# EasyFlybackRev2.net
KiCad netlist of a schematic drawn in EAGLE
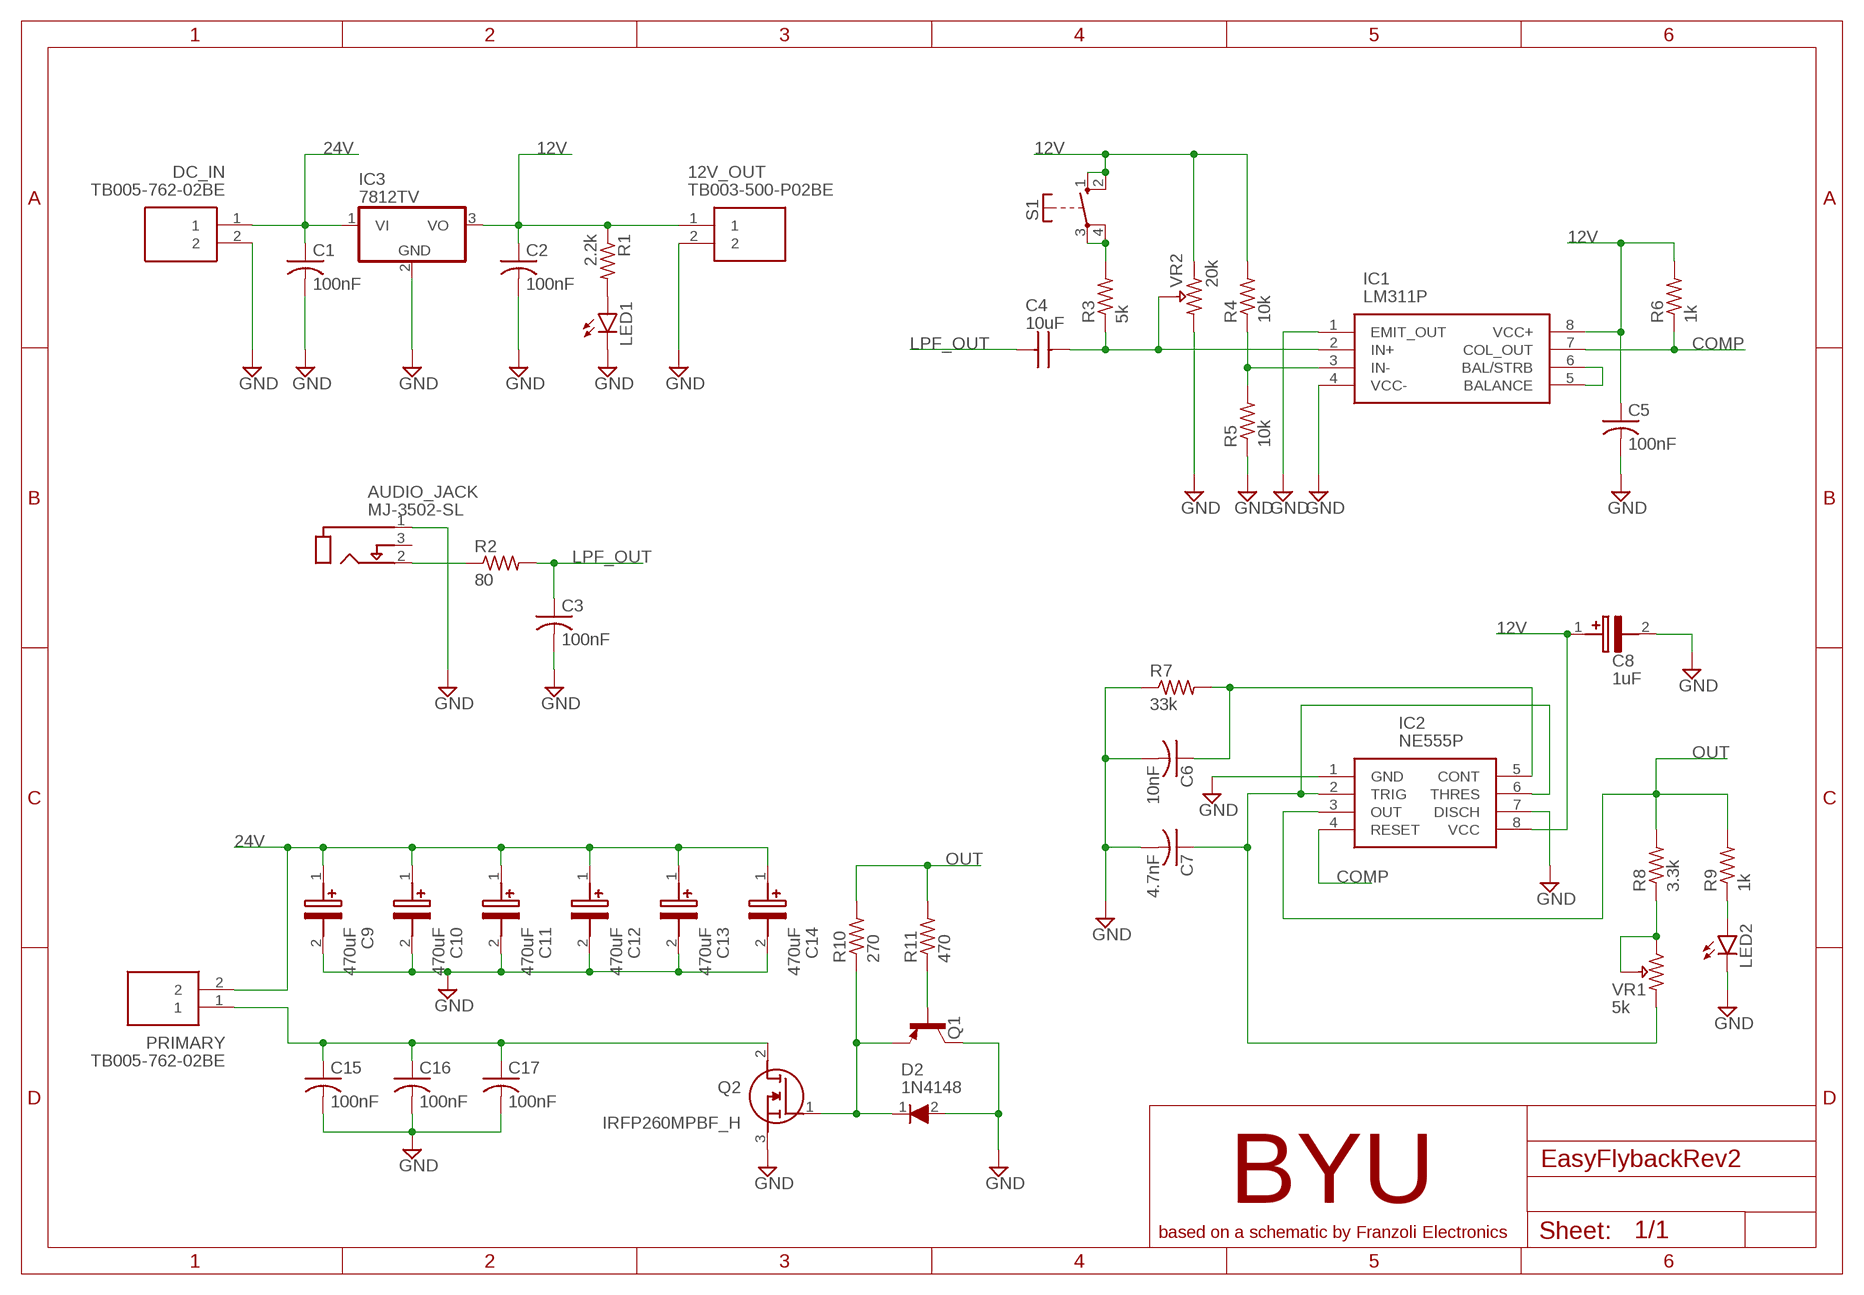
[diagram p0: schematic, sheet 1]

(export (version "E")
  (design (tool "Eeschema 10.0.6"))
  (components
    (comp (ref "12V_OUT")
      (value "TB003-500-P02BE")
      (footprint "eagle-import:SHDR2W100P0X500_1X2_1000X780X1")
      (fields (field (name "MOUSER_PART_NUMBER") "490-TB003-500-P02BE"))
      (libsource (lib "eagle-import") (part "TB003-500-P02BE"))
    )
    (comp (ref "AUDIO_JACK")
      (value "MJ-3502-SL")
      (footprint "eagle-import:MJ3502-SL")
      (fields (field (name "SPICEPREFIX") "J"))
      (libsource (lib "eagle-import") (part "MJ-3502-SL"))
    )
    (comp (ref "C1")
      (value "100nF")
      (footprint "eagle-import:C025-024X044")
      (libsource (lib "eagle-import") (part "C-US025-024X044"))
    )
    (comp (ref "C2")
      (value "100nF")
      (footprint "eagle-import:C025-024X044")
      (libsource (lib "eagle-import") (part "C-US025-024X044"))
    )
    (comp (ref "C3")
      (value "100nF")
      (footprint "eagle-import:C025-024X044")
      (libsource (lib "eagle-import") (part "C-US025-024X044"))
    )
    (comp (ref "C4")
      (value "10uF")
      (footprint "eagle-import:RCE7U2J103J3K1H03B")
      (fields
        (field (name "MANUFACTURER_PART_NUMBER") "RDEC71H106K3K1H03B")
        (field (name "MOUSER_PART_NUMBER") "81-RDEC71H106K3K1H3B")
      )
      (libsource (lib "eagle-import") (part "RDEC71H106K3K1H03B"))
    )
    (comp (ref "C5")
      (value "100nF")
      (footprint "eagle-import:C025-024X044")
      (libsource (lib "eagle-import") (part "C-US025-024X044"))
    )
    (comp (ref "C6")
      (value "10nF")
      (footprint "eagle-import:C025-024X044")
      (libsource (lib "eagle-import") (part "C-US025-024X044"))
    )
    (comp (ref "C7")
      (value "4.7nF")
      (footprint "eagle-import:C025-024X044")
      (libsource (lib "eagle-import") (part "C-US025-024X044"))
    )
    (comp (ref "C8")
      (value "1uF")
      (footprint "eagle-import:TAP105K035SCS")
      (fields
        (field (name "MANUFACTURER_PART_NUMBER") "TAP105K035SCS")
        (field (name "MOUSER_PART_NUMBER") "581-TAP105K035SCS")
      )
      (libsource (lib "eagle-import") (part "TAP105K035SCS"))
    )
    (comp (ref "C9")
      (value "470uF")
      (footprint "eagle-import:CAPPRD500W65D1000H1700")
      (fields
        (field (name "MANUFACTURER_PART_NUMBER") "ECA-1VM471B")
        (field (name "MOUSER_PART_NUMBER") "667-ECA-1VM471B")
      )
      (libsource (lib "eagle-import") (part "ECA-1VM471B"))
    )
    (comp (ref "C10")
      (value "470uF")
      (footprint "eagle-import:CAPPRD500W65D1000H1700")
      (fields
        (field (name "MANUFACTURER_PART_NUMBER") "ECA-1VM471B")
        (field (name "MOUSER_PART_NUMBER") "667-ECA-1VM471B")
      )
      (libsource (lib "eagle-import") (part "ECA-1VM471B"))
    )
    (comp (ref "C11")
      (value "470uF")
      (footprint "eagle-import:CAPPRD500W65D1000H1700")
      (fields
        (field (name "MANUFACTURER_PART_NUMBER") "ECA-1VM471B")
        (field (name "MOUSER_PART_NUMBER") "667-ECA-1VM471B")
      )
      (libsource (lib "eagle-import") (part "ECA-1VM471B"))
    )
    (comp (ref "C12")
      (value "470uF")
      (footprint "eagle-import:CAPPRD500W65D1000H1700")
      (fields
        (field (name "MANUFACTURER_PART_NUMBER") "ECA-1VM471B")
        (field (name "MOUSER_PART_NUMBER") "667-ECA-1VM471B")
      )
      (libsource (lib "eagle-import") (part "ECA-1VM471B"))
    )
    (comp (ref "C13")
      (value "470uF")
      (footprint "eagle-import:CAPPRD500W65D1000H1700")
      (fields
        (field (name "MANUFACTURER_PART_NUMBER") "ECA-1VM471B")
        (field (name "MOUSER_PART_NUMBER") "667-ECA-1VM471B")
      )
      (libsource (lib "eagle-import") (part "ECA-1VM471B"))
    )
    (comp (ref "C14")
      (value "470uF")
      (footprint "eagle-import:CAPPRD500W65D1000H1700")
      (fields
        (field (name "MANUFACTURER_PART_NUMBER") "ECA-1VM471B")
        (field (name "MOUSER_PART_NUMBER") "667-ECA-1VM471B")
      )
      (libsource (lib "eagle-import") (part "ECA-1VM471B"))
    )
    (comp (ref "C15")
      (value "100nF")
      (footprint "eagle-import:MKP1G031004D00KSSD")
      (libsource (lib "eagle-import") (part "MKP1G031004D00KSSD"))
    )
    (comp (ref "C16")
      (value "100nF")
      (footprint "eagle-import:MKP1G031004D00KSSD")
      (libsource (lib "eagle-import") (part "MKP1G031004D00KSSD"))
    )
    (comp (ref "C17")
      (value "100nF")
      (footprint "eagle-import:MKP1G031004D00KSSD")
      (libsource (lib "eagle-import") (part "MKP1G031004D00KSSD"))
    )
    (comp (ref "D2")
      (value "1N4148")
      (footprint "eagle-import:DIOAD1068W53L380D172")
      (fields (field (name "MOUSER_PART_NUMBER") "512-1N4148"))
      (libsource (lib "eagle-import") (part "1N4148"))
    )
    (comp (ref "DC_IN")
      (value "TB005-762-02BE")
      (footprint "eagle-import:TB00576202BE")
      (fields (field (name "MOUSER_PART_NUMBER") "490-TB005-762-02BE"))
      (libsource (lib "eagle-import") (part "TB005-762-02BE"))
    )
    (comp (ref "IC1")
      (value "LM311P")
      (footprint "eagle-import:DIP794W53P254L959H508Q8N")
      (fields (field (name "MOUSER_PART_NUMBER") "595-LM311P"))
      (libsource (lib "eagle-import") (part "LM311P"))
    )
    (comp (ref "IC2")
      (value "NE555P")
      (footprint "eagle-import:DIP794W53P254L959H508Q8N")
      (fields (field (name "MOUSER_PART_NUMBER") "595-NE555P"))
      (libsource (lib "eagle-import") (part "NE555P"))
    )
    (comp (ref "IC3")
      (value "7812TV")
      (footprint "eagle-import:TO220V")
      (libsource (lib "eagle-import") (part "78TV12"))
    )
    (comp (ref "LED1")
      (value "LED5MM")
      (footprint "eagle-import:LED5MM")
      (libsource (lib "eagle-import") (part "LED5MM"))
    )
    (comp (ref "LED2")
      (value "LED5MM")
      (footprint "eagle-import:LED5MM")
      (libsource (lib "eagle-import") (part "LED5MM"))
    )
    (comp (ref "PRIMARY")
      (value "TB005-762-02BE")
      (footprint "eagle-import:TB00576202BE")
      (fields (field (name "MOUSER_PART_NUMBER") "490-TB005-762-02BE"))
      (libsource (lib "eagle-import") (part "TB005-762-02BE"))
    )
    (comp (ref "Q1")
      (value "-PNP-TO92-E1")
      (footprint "eagle-import:TO92-E1")
      (libsource (lib "eagle-import") (part "-PNP-TO92-E1"))
    )
    (comp (ref "Q2")
      (value "IRFP260MPBF_H")
      (footprint "eagle-import:TO545P520X1594X2550-3P_H")
      (fields
        (field (name "MANUFACTURER_PART_NUMBER") "IRFP260MPBF")
        (field (name "MOUSER_PART_NUMBER") "942-IRFP260MPBF")
      )
      (libsource (lib "eagle-import") (part "IRFP260MPBF_H"))
    )
    (comp (ref "R1")
      (value "2.2k")
      (footprint "eagle-import:0207_10")
      (libsource (lib "eagle-import") (part "R-US_0207/10"))
    )
    (comp (ref "R2")
      (value "80")
      (footprint "eagle-import:0207_10")
      (libsource (lib "eagle-import") (part "R-US_0207/10"))
    )
    (comp (ref "R3")
      (value "5k")
      (footprint "eagle-import:0207_10")
      (libsource (lib "eagle-import") (part "R-US_0207/10"))
    )
    (comp (ref "R4")
      (value "10k")
      (footprint "eagle-import:0207_10")
      (libsource (lib "eagle-import") (part "R-US_0207/10"))
    )
    (comp (ref "R5")
      (value "10k")
      (footprint "eagle-import:0207_10")
      (libsource (lib "eagle-import") (part "R-US_0207/10"))
    )
    (comp (ref "R6")
      (value "1k")
      (footprint "eagle-import:0207_10")
      (libsource (lib "eagle-import") (part "R-US_0207/10"))
    )
    (comp (ref "R7")
      (value "33k")
      (footprint "eagle-import:0207_10")
      (libsource (lib "eagle-import") (part "R-US_0207/10"))
    )
    (comp (ref "R8")
      (value "3.3k")
      (footprint "eagle-import:0207_10")
      (libsource (lib "eagle-import") (part "R-US_0207/10"))
    )
    (comp (ref "R9")
      (value "1k")
      (footprint "eagle-import:0207_10")
      (libsource (lib "eagle-import") (part "R-US_0207/10"))
    )
    (comp (ref "R10")
      (value "270")
      (footprint "eagle-import:0207_10")
      (libsource (lib "eagle-import") (part "R-US_0207/10"))
    )
    (comp (ref "R11")
      (value "470")
      (footprint "eagle-import:0207_10")
      (libsource (lib "eagle-import") (part "R-US_0207/10"))
    )
    (comp (ref "S1")
      (value "DTE6K")
      (footprint "eagle-import:DTE6K")
      (libsource (lib "eagle-import") (part "DTE6K"))
    )
    (comp (ref "VR1")
      (value "5k")
      (footprint "eagle-import:PV36W502C01B00")
      (fields
        (field (name "MANUFACTURER_PART_NUMBER") "PV36W502C01B00")
        (field (name "MOUSER_PART_NUMBER") "81-PV36W502C01B00")
      )
      (libsource (lib "eagle-import") (part "PV36W502C01B00"))
    )
    (comp (ref "VR2")
      (value "20k")
      (footprint "eagle-import:PV36W502C01B00")
      (fields
        (field (name "MANUFACTURER_PART_NUMBER") "PV36W502C01B00")
        (field (name "MOUSER_PART_NUMBER") "81-PV36W502C01B00")
      )
      (libsource (lib "eagle-import") (part "PV36W502C01B00"))
    )
  )
  (nets
    (net (code "1") (name "/12V") (class "Default")
      (node (ref "12V_OUT") (pin "1") (pinfunction "1_1") (pintype "bidirectional"))
      (node (ref "C2") (pin "1") (pinfunction "1_1") (pintype "passive"))
      (node (ref "C5") (pin "1") (pinfunction "1_1") (pintype "passive"))
      (node (ref "C8") (pin "1") (pinfunction "+_1") (pintype "bidirectional"))
      (node (ref "IC1") (pin "8") (pinfunction "VCC+_8") (pintype "bidirectional"))
      (node (ref "IC2") (pin "8") (pinfunction "VCC_8") (pintype "bidirectional"))
      (node (ref "IC3") (pin "3") (pinfunction "VO_3") (pintype "passive"))
      (node (ref "R1") (pin "1") (pinfunction "1_1") (pintype "passive"))
      (node (ref "R4") (pin "2") (pinfunction "2_2") (pintype "passive"))
      (node (ref "R6") (pin "2") (pinfunction "2_2") (pintype "passive"))
      (node (ref "S1") (pin "1") (pinfunction "S_1") (pintype "passive"))
      (node (ref "S1") (pin "2") (pinfunction "S_2") (pintype "passive"))
      (node (ref "VR2") (pin "1") (pinfunction "CCW_1") (pintype "bidirectional"))
    )
    (net (code "2") (name "/24V") (class "Default")
      (node (ref "C1") (pin "1") (pinfunction "1_1") (pintype "passive"))
      (node (ref "C10") (pin "1") (pinfunction "+_1") (pintype "bidirectional"))
      (node (ref "C11") (pin "1") (pinfunction "+_1") (pintype "bidirectional"))
      (node (ref "C12") (pin "1") (pinfunction "+_1") (pintype "bidirectional"))
      (node (ref "C13") (pin "1") (pinfunction "+_1") (pintype "bidirectional"))
      (node (ref "C14") (pin "1") (pinfunction "+_1") (pintype "bidirectional"))
      (node (ref "C9") (pin "1") (pinfunction "+_1") (pintype "bidirectional"))
      (node (ref "DC_IN") (pin "1") (pinfunction "1_1") (pintype "bidirectional"))
      (node (ref "IC3") (pin "1") (pinfunction "VI_1") (pintype "input"))
      (node (ref "PRIMARY") (pin "2") (pinfunction "2_2") (pintype "bidirectional"))
    )
    (net (code "3") (name "/COMP") (class "Default")
      (node (ref "IC1") (pin "7") (pinfunction "COL_OUT_7") (pintype "bidirectional"))
      (node (ref "IC2") (pin "4") (pinfunction "RESET_4") (pintype "bidirectional"))
      (node (ref "R6") (pin "1") (pinfunction "1_1") (pintype "passive"))
    )
    (net (code "4") (name "/LPF_OUT") (class "Default")
      (node (ref "C3") (pin "1") (pinfunction "1_1") (pintype "passive"))
      (node (ref "C4") (pin "1") (pinfunction "1_1") (pintype "bidirectional"))
      (node (ref "R2") (pin "2") (pinfunction "2_2") (pintype "passive"))
    )
    (net (code "5") (name "/OUT") (class "Default")
      (node (ref "IC2") (pin "3") (pinfunction "OUT_3") (pintype "bidirectional"))
      (node (ref "R10") (pin "2") (pinfunction "2_2") (pintype "passive"))
      (node (ref "R11") (pin "2") (pinfunction "2_2") (pintype "passive"))
      (node (ref "R8") (pin "2") (pinfunction "2_2") (pintype "passive"))
      (node (ref "R9") (pin "2") (pinfunction "2_2") (pintype "passive"))
    )
    (net (code "6") (name "GND") (class "Default")
      (node (ref "12V_OUT") (pin "2") (pinfunction "2_2") (pintype "bidirectional"))
      (node (ref "AUDIO_JACK") (pin "1") (pinfunction "1_1") (pintype "bidirectional"))
      (node (ref "C1") (pin "2") (pinfunction "2_2") (pintype "passive"))
      (node (ref "C10") (pin "2") (pinfunction "-_2") (pintype "bidirectional"))
      (node (ref "C11") (pin "2") (pinfunction "-_2") (pintype "bidirectional"))
      (node (ref "C12") (pin "2") (pinfunction "-_2") (pintype "bidirectional"))
      (node (ref "C13") (pin "2") (pinfunction "-_2") (pintype "bidirectional"))
      (node (ref "C14") (pin "2") (pinfunction "-_2") (pintype "bidirectional"))
      (node (ref "C15") (pin "P$2") (pinfunction "2_P$2") (pintype "passive"))
      (node (ref "C16") (pin "P$2") (pinfunction "2_P$2") (pintype "passive"))
      (node (ref "C17") (pin "P$2") (pinfunction "2_P$2") (pintype "passive"))
      (node (ref "C2") (pin "2") (pinfunction "2_2") (pintype "passive"))
      (node (ref "C3") (pin "2") (pinfunction "2_2") (pintype "passive"))
      (node (ref "C5") (pin "2") (pinfunction "2_2") (pintype "passive"))
      (node (ref "C6") (pin "2") (pinfunction "2_2") (pintype "passive"))
      (node (ref "C7") (pin "2") (pinfunction "2_2") (pintype "passive"))
      (node (ref "C8") (pin "2") (pinfunction "-_2") (pintype "bidirectional"))
      (node (ref "C9") (pin "2") (pinfunction "-_2") (pintype "bidirectional"))
      (node (ref "D2") (pin "2") (pinfunction "A_2") (pintype "bidirectional"))
      (node (ref "DC_IN") (pin "2") (pinfunction "2_2") (pintype "bidirectional"))
      (node (ref "IC1") (pin "1") (pinfunction "EMIT_OUT_1") (pintype "bidirectional"))
      (node (ref "IC1") (pin "4") (pinfunction "VCC-_4") (pintype "bidirectional"))
      (node (ref "IC2") (pin "1") (pinfunction "GND_1") (pintype "bidirectional"))
      (node (ref "IC2") (pin "7") (pinfunction "DISCH_7") (pintype "bidirectional"))
      (node (ref "IC3") (pin "2") (pinfunction "GND_2") (pintype "passive"))
      (node (ref "LED1") (pin "K") (pinfunction "C_K") (pintype "passive"))
      (node (ref "LED2") (pin "K") (pinfunction "C_K") (pintype "passive"))
      (node (ref "Q1") (pin "1") (pinfunction "C_1") (pintype "passive"))
      (node (ref "Q2") (pin "3") (pinfunction "S_3") (pintype "bidirectional"))
      (node (ref "R5") (pin "1") (pinfunction "1_1") (pintype "passive"))
      (node (ref "R7") (pin "1") (pinfunction "1_1") (pintype "passive"))
      (node (ref "VR2") (pin "3") (pinfunction "CW_3") (pintype "bidirectional"))
    )
    (net (code "7") (name "Net-(AUDIO_JACK-Pad2)") (class "Default")
      (node (ref "AUDIO_JACK") (pin "2") (pinfunction "2_2") (pintype "bidirectional"))
      (node (ref "R2") (pin "1") (pinfunction "1_1") (pintype "passive"))
    )
    (net (code "8") (name "Net-(C15-1)") (class "Default")
      (node (ref "C15") (pin "P$1") (pinfunction "1_P$1") (pintype "passive"))
      (node (ref "C16") (pin "P$1") (pinfunction "1_P$1") (pintype "passive"))
      (node (ref "C17") (pin "P$1") (pinfunction "1_P$1") (pintype "passive"))
      (node (ref "PRIMARY") (pin "1") (pinfunction "1_1") (pintype "bidirectional"))
      (node (ref "Q2") (pin "2") (pinfunction "D_2") (pintype "bidirectional"))
    )
    (net (code "9") (name "Net-(D2-K)") (class "Default")
      (node (ref "D2") (pin "1") (pinfunction "K_1") (pintype "bidirectional"))
      (node (ref "Q1") (pin "3") (pinfunction "E_3") (pintype "passive"))
      (node (ref "Q2") (pin "1") (pinfunction "G_1") (pintype "bidirectional"))
      (node (ref "R10") (pin "1") (pinfunction "1_1") (pintype "passive"))
    )
    (net (code "10") (name "Net-(IC1-BALANCE)") (class "Default")
      (node (ref "IC1") (pin "5") (pinfunction "BALANCE_5") (pintype "bidirectional"))
      (node (ref "IC1") (pin "6") (pinfunction "BAL/STRB_6") (pintype "bidirectional"))
    )
    (net (code "11") (name "Net-(IC1-IN+)") (class "Default")
      (node (ref "C4") (pin "2") (pinfunction "2_2") (pintype "bidirectional"))
      (node (ref "IC1") (pin "2") (pinfunction "IN+_2") (pintype "bidirectional"))
      (node (ref "R3") (pin "1") (pinfunction "1_1") (pintype "passive"))
      (node (ref "VR2") (pin "2") (pinfunction "WIPER_2") (pintype "bidirectional"))
    )
    (net (code "12") (name "Net-(IC1-IN-)") (class "Default")
      (node (ref "IC1") (pin "3") (pinfunction "IN-_3") (pintype "bidirectional"))
      (node (ref "R4") (pin "1") (pinfunction "1_1") (pintype "passive"))
      (node (ref "R5") (pin "2") (pinfunction "2_2") (pintype "passive"))
    )
    (net (code "13") (name "Net-(IC2-CONT)") (class "Default")
      (node (ref "C6") (pin "1") (pinfunction "1_1") (pintype "passive"))
      (node (ref "IC2") (pin "5") (pinfunction "CONT_5") (pintype "bidirectional"))
      (node (ref "R7") (pin "2") (pinfunction "2_2") (pintype "passive"))
    )
    (net (code "14") (name "Net-(IC2-THRES)") (class "Default")
      (node (ref "C7") (pin "1") (pinfunction "1_1") (pintype "passive"))
      (node (ref "IC2") (pin "2") (pinfunction "TRIG_2") (pintype "bidirectional"))
      (node (ref "IC2") (pin "6") (pinfunction "THRES_6") (pintype "bidirectional"))
      (node (ref "VR1") (pin "3") (pinfunction "CW_3") (pintype "bidirectional"))
    )
    (net (code "15") (name "Net-(LED1-PadA)") (class "Default")
      (node (ref "LED1") (pin "A") (pinfunction "A_A") (pintype "passive"))
      (node (ref "R1") (pin "2") (pinfunction "2_2") (pintype "passive"))
    )
    (net (code "16") (name "Net-(LED2-PadA)") (class "Default")
      (node (ref "LED2") (pin "A") (pinfunction "A_A") (pintype "passive"))
      (node (ref "R9") (pin "1") (pinfunction "1_1") (pintype "passive"))
    )
    (net (code "17") (name "Net-(Q1-B)") (class "Default")
      (node (ref "Q1") (pin "2") (pinfunction "B_2") (pintype "passive"))
      (node (ref "R11") (pin "1") (pinfunction "1_1") (pintype "passive"))
    )
    (net (code "18") (name "Net-(R3-Pad2)") (class "Default")
      (node (ref "R3") (pin "2") (pinfunction "2_2") (pintype "passive"))
      (node (ref "S1") (pin "3") (pinfunction "P_3") (pintype "passive"))
      (node (ref "S1") (pin "4") (pinfunction "P_4") (pintype "passive"))
    )
    (net (code "19") (name "Net-(VR1-CCW)") (class "Default")
      (node (ref "R8") (pin "1") (pinfunction "1_1") (pintype "passive"))
      (node (ref "VR1") (pin "1") (pinfunction "CCW_1") (pintype "bidirectional"))
      (node (ref "VR1") (pin "2") (pinfunction "WIPER_2") (pintype "bidirectional"))
    )
    (net (code "20") (name "unconnected-(AUDIO_JACK-Pad3)") (class "Default")
      (node (ref "AUDIO_JACK") (pin "3") (pinfunction "3_3") (pintype "bidirectional"))
    )
  )
)
